# eagle_8_test.net
KiCad netlist of a schematic drawn in EAGLE
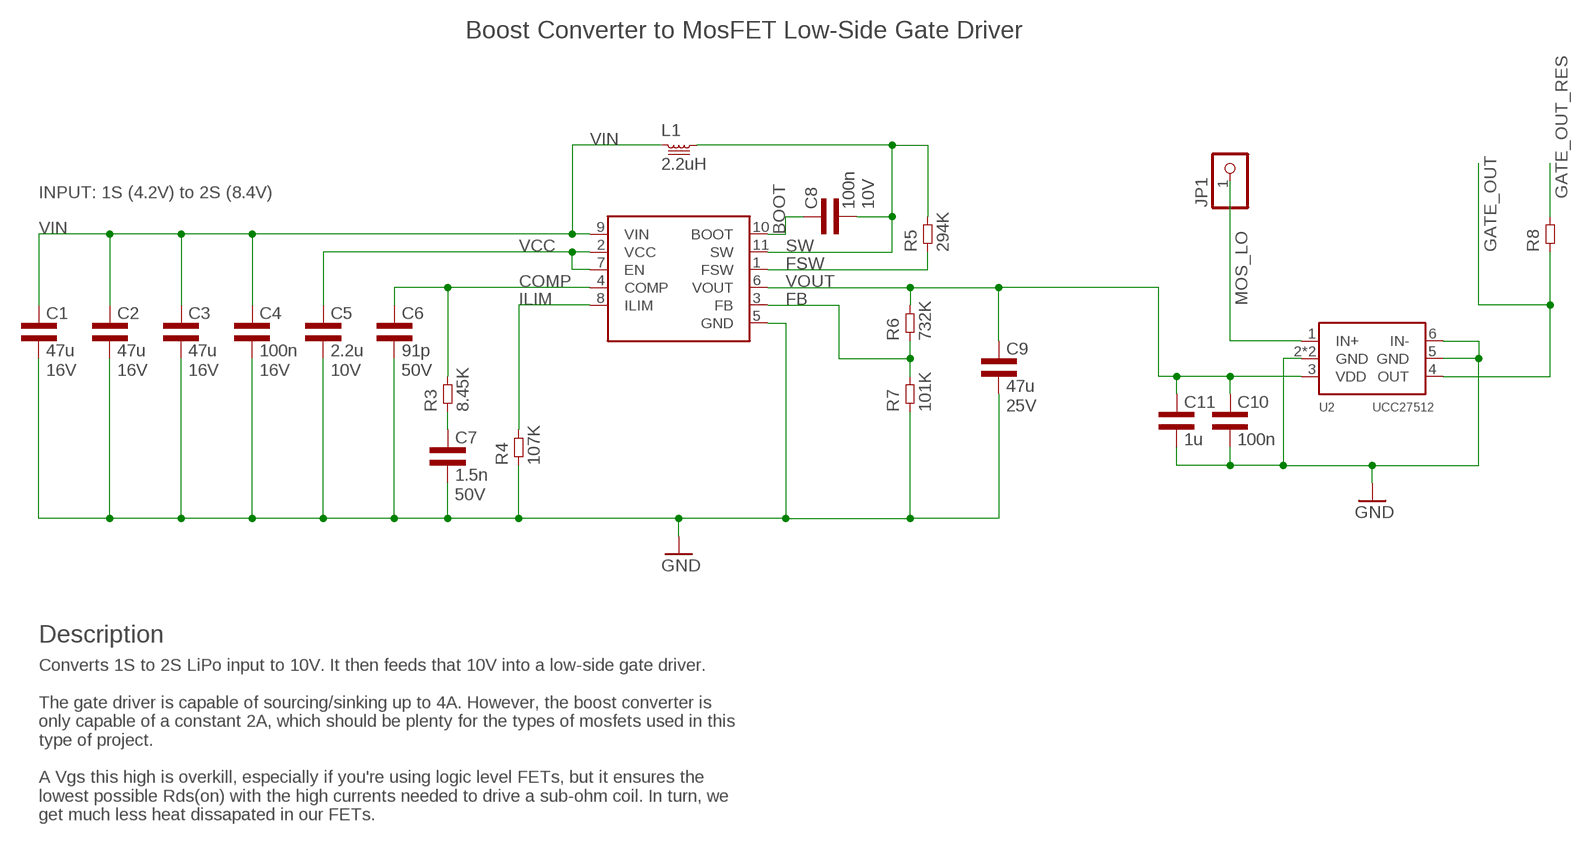
[diagram p0: schematic, sheet 1]

(export (version "E")
  (design (tool "Eeschema 10.0.6"))
  (components
    (comp (ref "C1")
      (value "47u")
      (footprint "eagle-import:1210L3")
      (fields (field (name "VOLTAGE") "16V"))
      (libsource (lib "eagle-import") (part "CAP1210L3"))
    )
    (comp (ref "C2")
      (value "47u")
      (footprint "eagle-import:1210L3")
      (fields (field (name "VOLTAGE") "16V"))
      (libsource (lib "eagle-import") (part "CAP1210L3"))
    )
    (comp (ref "C3")
      (value "47u")
      (footprint "eagle-import:1210L3")
      (fields (field (name "VOLTAGE") "16V"))
      (libsource (lib "eagle-import") (part "CAP1210L3"))
    )
    (comp (ref "C4")
      (value "100n")
      (footprint "eagle-import:0402L3")
      (fields (field (name "VOLTAGE") "16V"))
      (libsource (lib "eagle-import") (part "CAP0402L3"))
    )
    (comp (ref "C5")
      (value "2.2u")
      (footprint "eagle-import:0603L3")
      (fields (field (name "VOLTAGE") "10V"))
      (libsource (lib "eagle-import") (part "CAP0603L3"))
    )
    (comp (ref "C6")
      (value "91p")
      (footprint "eagle-import:0805L3")
      (fields (field (name "VOLTAGE") "50V"))
      (libsource (lib "eagle-import") (part "CAP0805L3"))
    )
    (comp (ref "C7")
      (value "1.5n")
      (footprint "eagle-import:0805L3")
      (fields (field (name "VOLTAGE") "50V"))
      (libsource (lib "eagle-import") (part "CAP0805L3"))
    )
    (comp (ref "C8")
      (value "100n")
      (footprint "eagle-import:0402L3")
      (fields (field (name "VOLTAGE") "10V"))
      (libsource (lib "eagle-import") (part "CAP0402L3"))
    )
    (comp (ref "C9")
      (value "47u")
      (footprint "eagle-import:1206L3")
      (fields (field (name "VOLTAGE") "25V"))
      (libsource (lib "eagle-import") (part "CAP1206L3"))
    )
    (comp (ref "C10")
      (value "100n")
      (footprint "eagle-import:0603L3")
      (libsource (lib "eagle-import") (part "CAP0603L3"))
    )
    (comp (ref "C11")
      (value "1u")
      (footprint "eagle-import:0805L3")
      (libsource (lib "eagle-import") (part "CAP0805L3"))
    )
    (comp (ref "JP1")
      (value "PINHD-1X1")
      (footprint "eagle-import:1X01")
      (libsource (lib "eagle-import") (part "PINHD-1X1"))
    )
    (comp (ref "L1")
      (value "2.2uH")
      (footprint "eagle-import:9.2X8.5")
      (libsource (lib "eagle-import") (part "INDUCTOR9.2X8.5"))
    )
    (comp (ref "R3")
      (value "8.45K")
      (footprint "eagle-import:0402L3")
      (libsource (lib "eagle-import") (part "RES0402L3"))
    )
    (comp (ref "R4")
      (value "107K")
      (footprint "eagle-import:1206L3")
      (libsource (lib "eagle-import") (part "RES1206L3"))
    )
    (comp (ref "R5")
      (value "294K")
      (footprint "eagle-import:1206L3")
      (libsource (lib "eagle-import") (part "RES1206L3"))
    )
    (comp (ref "R6")
      (value "732K")
      (footprint "eagle-import:0402L3")
      (libsource (lib "eagle-import") (part "RES0402L3"))
    )
    (comp (ref "R7")
      (value "101K")
      (footprint "eagle-import:0805L3")
      (libsource (lib "eagle-import") (part "RES0805L3"))
    )
    (comp (ref "R8")
      (value "RES1206L3")
      (footprint "eagle-import:1206L3")
      (libsource (lib "eagle-import") (part "RES1206L3"))
    )
    (comp (ref "U1")
      (value "TPS61089")
      (footprint "eagle-import:VQFN-11")
      (libsource (lib "eagle-import") (part "TPS61089"))
    )
    (comp (ref "U2")
      (value "UCC27512")
      (footprint "eagle-import:S-PWSON-N6")
      (libsource (lib "eagle-import") (part "UCC27512"))
    )
  )
  (nets
    (net (code "1") (name "/BOOT") (class "Default")
      (node (ref "C8") (pin "P$1") (pinfunction "1_P$1") (pintype "bidirectional"))
      (node (ref "U1") (pin "10") (pinfunction "BOOT_10") (pintype "bidirectional"))
    )
    (net (code "2") (name "/COMP") (class "Default")
      (node (ref "C6") (pin "1") (pinfunction "1_1") (pintype "bidirectional"))
      (node (ref "R3") (pin "P$2") (pinfunction "2_P$2") (pintype "bidirectional"))
      (node (ref "U1") (pin "4") (pinfunction "COMP_4") (pintype "bidirectional"))
    )
    (net (code "3") (name "/FB") (class "Default")
      (node (ref "R6") (pin "P$1") (pinfunction "1_P$1") (pintype "bidirectional"))
      (node (ref "R7") (pin "2") (pinfunction "2_2") (pintype "bidirectional"))
      (node (ref "U1") (pin "3") (pinfunction "FB_3") (pintype "bidirectional"))
    )
    (net (code "4") (name "/FSW") (class "Default")
      (node (ref "R5") (pin "1") (pinfunction "1_1") (pintype "bidirectional"))
      (node (ref "U1") (pin "1") (pinfunction "FSW_1") (pintype "bidirectional"))
    )
    (net (code "5") (name "/GATE_OUT") (class "Default")
      (node (ref "R8") (pin "1") (pinfunction "1_1") (pintype "bidirectional"))
      (node (ref "U2") (pin "4") (pinfunction "OUT_4") (pintype "bidirectional"))
    )
    (net (code "6") (name "/GATE_OUT_RES") (class "Default")
      (node (ref "R8") (pin "2") (pinfunction "2_2") (pintype "bidirectional"))
    )
    (net (code "7") (name "/ILIM") (class "Default")
      (node (ref "R4") (pin "2") (pinfunction "2_2") (pintype "bidirectional"))
      (node (ref "U1") (pin "8") (pinfunction "ILIM_8") (pintype "bidirectional"))
    )
    (net (code "8") (name "/MOS_LO") (class "Default")
      (node (ref "JP1") (pin "1") (pinfunction "1_1") (pintype "passive"))
      (node (ref "U2") (pin "1") (pinfunction "IN+_1") (pintype "bidirectional"))
    )
    (net (code "9") (name "/SW") (class "Default")
      (node (ref "C8") (pin "P$2") (pinfunction "2_P$2") (pintype "bidirectional"))
      (node (ref "L1") (pin "2") (pinfunction "2_2") (pintype "bidirectional"))
      (node (ref "R5") (pin "2") (pinfunction "2_2") (pintype "bidirectional"))
      (node (ref "U1") (pin "11") (pinfunction "SW_11") (pintype "bidirectional"))
    )
    (net (code "10") (name "/VCC") (class "Default")
      (node (ref "C5") (pin "P$1") (pinfunction "1_P$1") (pintype "bidirectional"))
      (node (ref "U1") (pin "2") (pinfunction "VCC_2") (pintype "bidirectional"))
      (node (ref "U1") (pin "7") (pinfunction "EN_7") (pintype "bidirectional"))
    )
    (net (code "11") (name "/VIN") (class "Default")
      (node (ref "C1") (pin "P$1") (pinfunction "1_P$1") (pintype "bidirectional"))
      (node (ref "C2") (pin "P$1") (pinfunction "1_P$1") (pintype "bidirectional"))
      (node (ref "C3") (pin "P$1") (pinfunction "1_P$1") (pintype "bidirectional"))
      (node (ref "C4") (pin "P$1") (pinfunction "1_P$1") (pintype "bidirectional"))
      (node (ref "L1") (pin "1") (pinfunction "1_1") (pintype "bidirectional"))
      (node (ref "U1") (pin "9") (pinfunction "VIN_9") (pintype "bidirectional"))
    )
    (net (code "12") (name "/VOUT") (class "Default")
      (node (ref "C10") (pin "P$1") (pinfunction "1_P$1") (pintype "bidirectional"))
      (node (ref "C11") (pin "1") (pinfunction "1_1") (pintype "bidirectional"))
      (node (ref "C9") (pin "1") (pinfunction "1_1") (pintype "bidirectional"))
      (node (ref "R6") (pin "P$2") (pinfunction "2_P$2") (pintype "bidirectional"))
      (node (ref "U1") (pin "6") (pinfunction "VOUT_6") (pintype "bidirectional"))
      (node (ref "U2") (pin "3") (pinfunction "VDD_3") (pintype "bidirectional"))
    )
    (net (code "13") (name "GND") (class "Default")
      (node (ref "C1") (pin "P$2") (pinfunction "2_P$2") (pintype "bidirectional"))
      (node (ref "C10") (pin "P$2") (pinfunction "2_P$2") (pintype "bidirectional"))
      (node (ref "C11") (pin "2") (pinfunction "2_2") (pintype "bidirectional"))
      (node (ref "C2") (pin "P$2") (pinfunction "2_P$2") (pintype "bidirectional"))
      (node (ref "C3") (pin "P$2") (pinfunction "2_P$2") (pintype "bidirectional"))
      (node (ref "C4") (pin "P$2") (pinfunction "2_P$2") (pintype "bidirectional"))
      (node (ref "C5") (pin "P$2") (pinfunction "2_P$2") (pintype "bidirectional"))
      (node (ref "C6") (pin "2") (pinfunction "2_2") (pintype "bidirectional"))
      (node (ref "C7") (pin "2") (pinfunction "2_2") (pintype "bidirectional"))
      (node (ref "C9") (pin "2") (pinfunction "2_2") (pintype "bidirectional"))
      (node (ref "R4") (pin "1") (pinfunction "1_1") (pintype "bidirectional"))
      (node (ref "R7") (pin "1") (pinfunction "1_1") (pintype "bidirectional"))
      (node (ref "U1") (pin "5") (pinfunction "GND_5") (pintype "bidirectional"))
      (node (ref "U2") (pin "2") (pinfunction "GND_2") (pintype "bidirectional"))
      (node (ref "U2") (pin "5") (pinfunction "GND_5") (pintype "bidirectional"))
      (node (ref "U2") (pin "6") (pinfunction "IN-_6") (pintype "bidirectional"))
      (node (ref "U2") (pin "TP") (pinfunction "GND_TP") (pintype "bidirectional"))
    )
    (net (code "14") (name "Net-(R3-1)") (class "Default")
      (node (ref "C7") (pin "1") (pinfunction "1_1") (pintype "bidirectional"))
      (node (ref "R3") (pin "P$1") (pinfunction "1_P$1") (pintype "bidirectional"))
    )
  )
)
